# TMS34010_Adapter_for_DE10_Nano.net
KiCad netlist of a schematic drawn in EAGLE
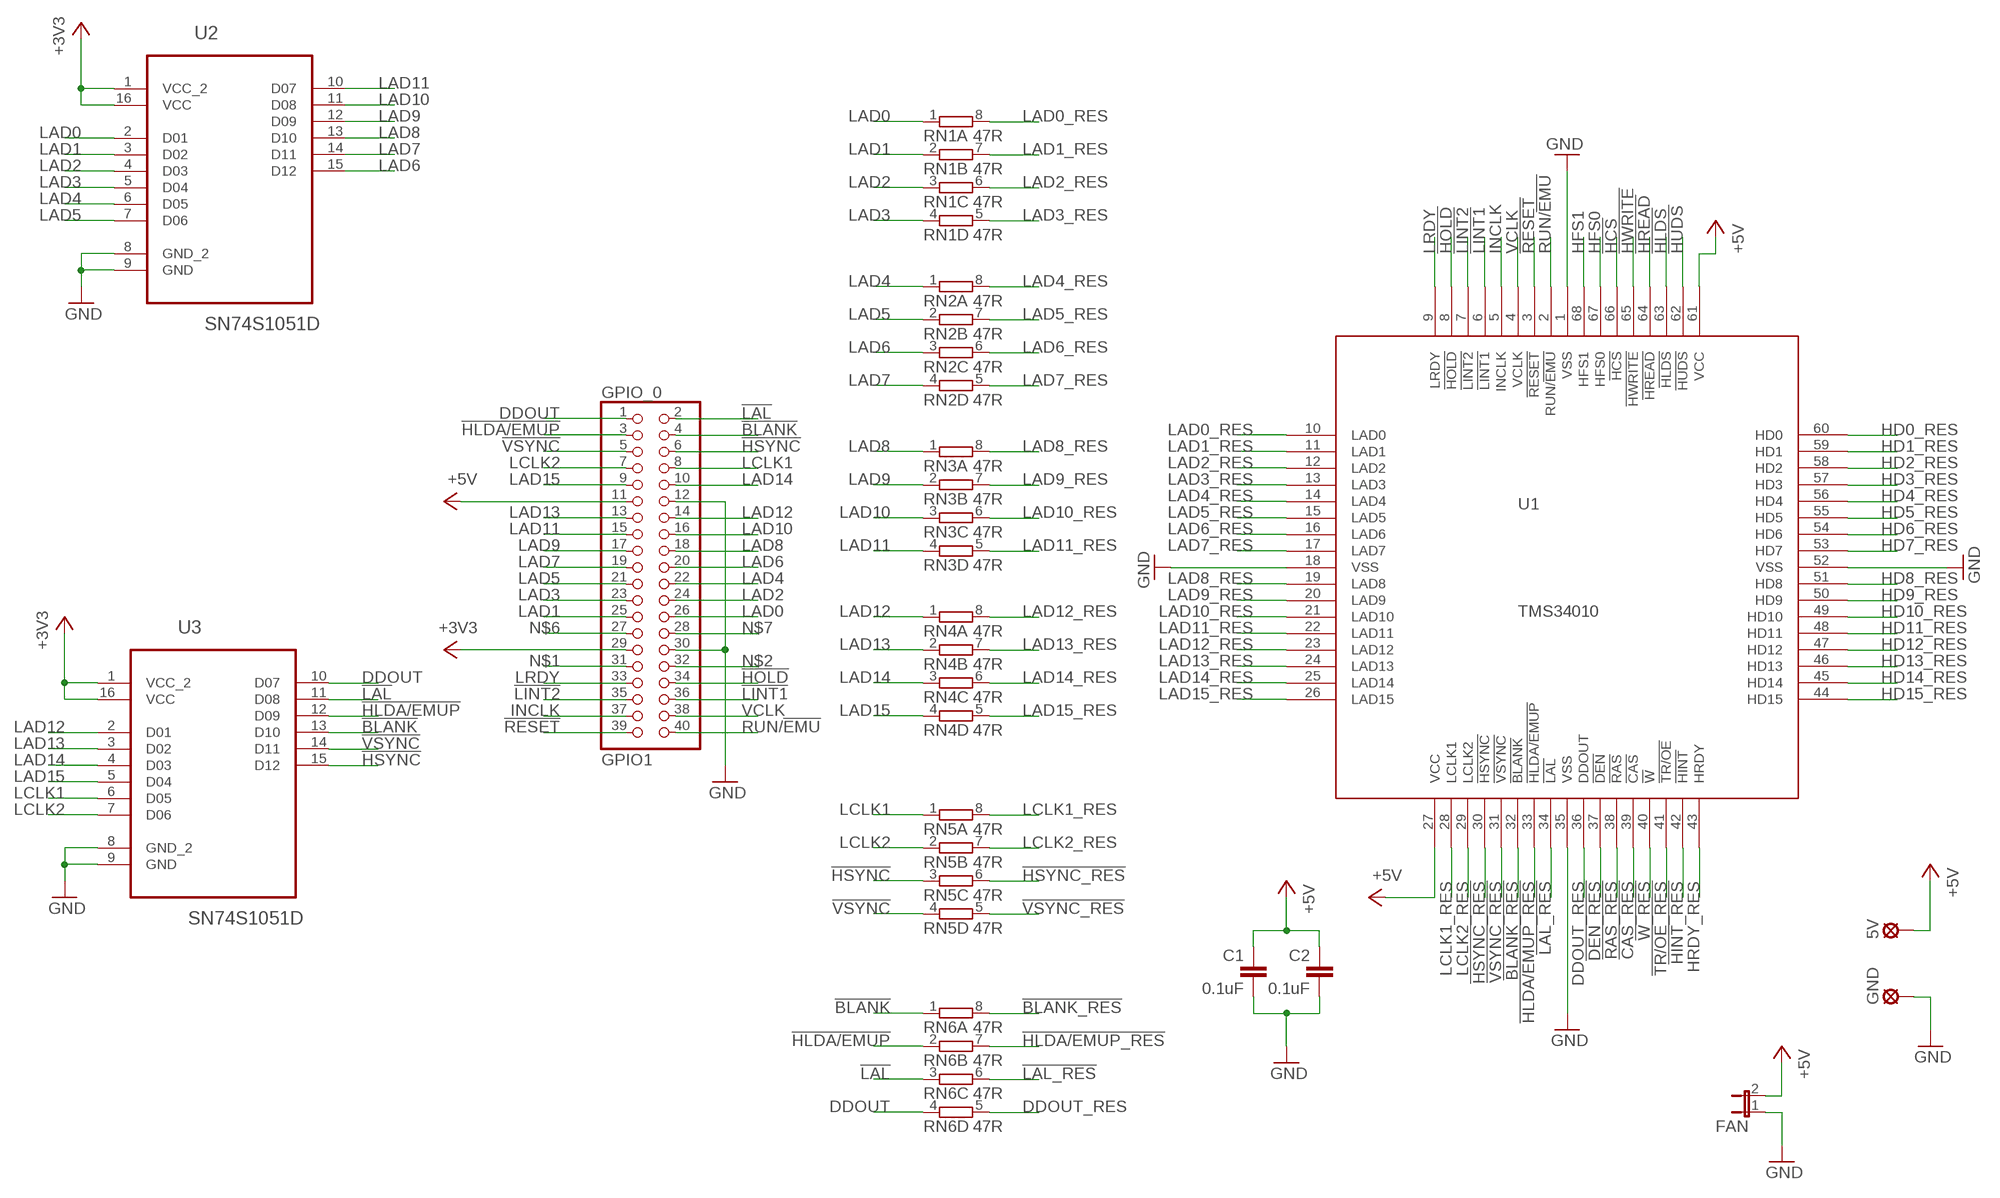
[diagram p0: schematic, sheet 1, part 1 of 2]
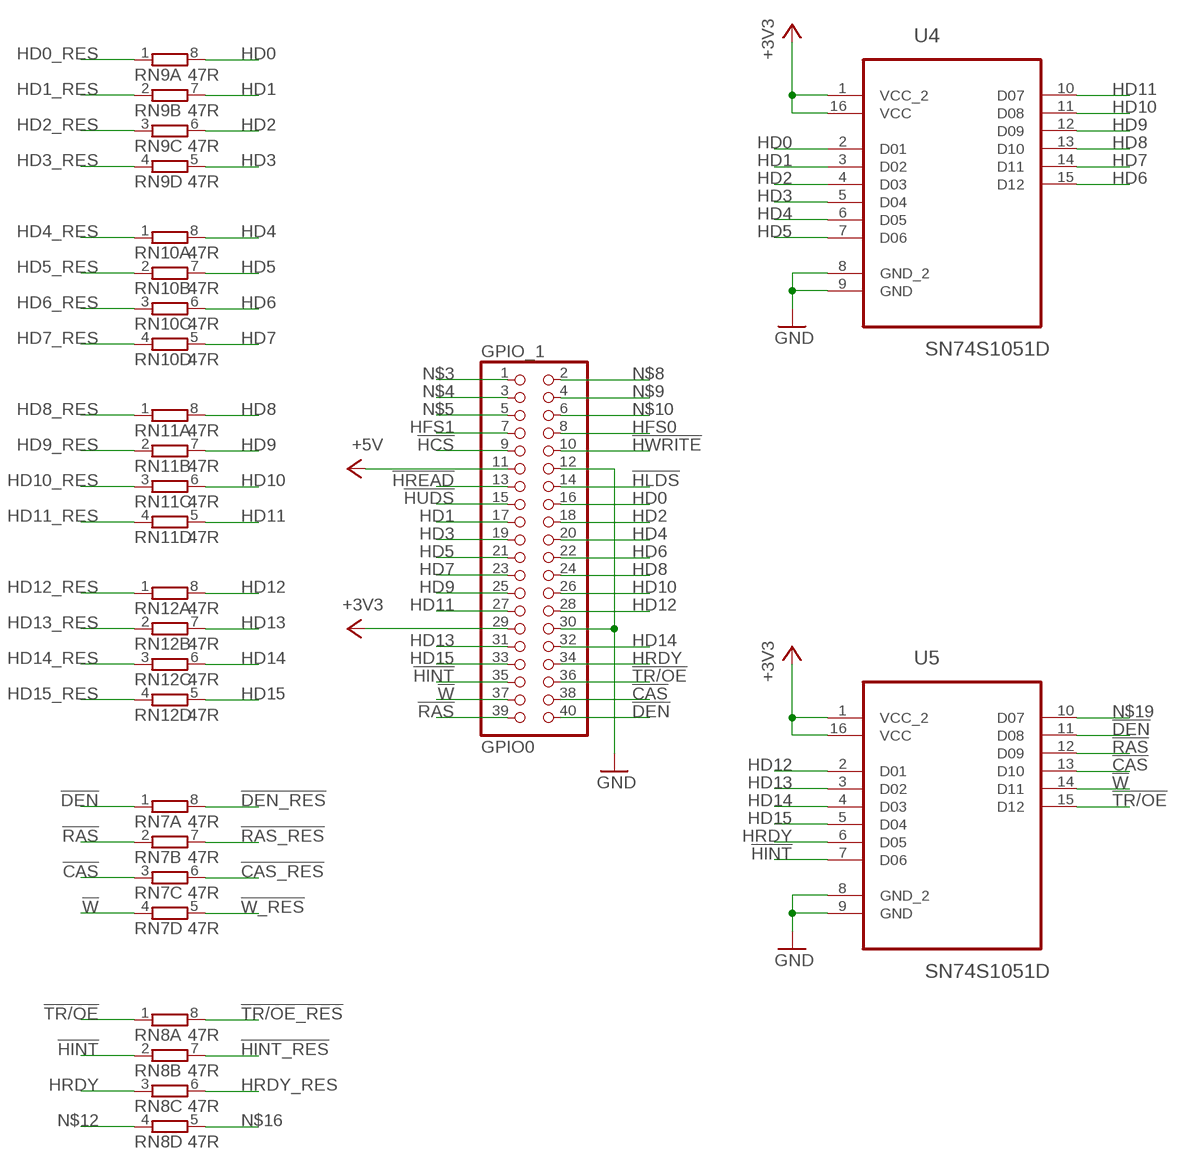
[diagram p1: schematic, sheet 1, part 2 of 2]

(export (version "E")
  (design (tool "Eeschema 10.0.6"))
  (components
    (comp (ref "5V")
      (value "LSP13")
      (footprint "eagle-import:LSP13")
      (libsource (lib "eagle-import") (part "LSP13"))
    )
    (comp (ref "C1")
      (value "0.1uF")
      (footprint "eagle-import:C0603")
      (libsource (lib "eagle-import") (part "C-EUC0603"))
    )
    (comp (ref "C2")
      (value "0.1uF")
      (footprint "eagle-import:C0603")
      (libsource (lib "eagle-import") (part "C-EUC0603"))
    )
    (comp (ref "FAN")
      (value "JP1E")
      (footprint "eagle-import:JP1")
      (libsource (lib "eagle-import") (part "JP1E"))
    )
    (comp (ref "GND")
      (value "LSP13")
      (footprint "eagle-import:LSP13")
      (libsource (lib "eagle-import") (part "LSP13"))
    )
    (comp (ref "GPIO_0")
      (value "GPIO1")
      (footprint "eagle-import:2X20")
      (libsource (lib "eagle-import") (part "PINHD-2X20"))
    )
    (comp (ref "GPIO_1")
      (value "GPIO0")
      (footprint "eagle-import:2X20")
      (libsource (lib "eagle-import") (part "PINHD-2X20"))
    )
    (comp (ref "RN1")
      (value "47R")
      (footprint "eagle-import:EXBV8V")
      (libsource (lib "eagle-import") (part "4R-NEXBV8V"))
    )
    (comp (ref "RN2")
      (value "47R")
      (footprint "eagle-import:EXBV8V")
      (libsource (lib "eagle-import") (part "4R-NEXBV8V"))
    )
    (comp (ref "RN3")
      (value "47R")
      (footprint "eagle-import:EXBV8V")
      (libsource (lib "eagle-import") (part "4R-NEXBV8V"))
    )
    (comp (ref "RN4")
      (value "47R")
      (footprint "eagle-import:EXBV8V")
      (libsource (lib "eagle-import") (part "4R-NEXBV8V"))
    )
    (comp (ref "RN5")
      (value "47R")
      (footprint "eagle-import:EXBV8V")
      (libsource (lib "eagle-import") (part "4R-NEXBV8V"))
    )
    (comp (ref "RN6")
      (value "47R")
      (footprint "eagle-import:EXBV8V")
      (libsource (lib "eagle-import") (part "4R-NEXBV8V"))
    )
    (comp (ref "RN7")
      (value "47R")
      (footprint "eagle-import:EXBV8V")
      (libsource (lib "eagle-import") (part "4R-NEXBV8V"))
    )
    (comp (ref "RN8")
      (value "47R")
      (footprint "eagle-import:EXBV8V")
      (libsource (lib "eagle-import") (part "4R-NEXBV8V"))
    )
    (comp (ref "RN9")
      (value "47R")
      (footprint "eagle-import:EXBV8V")
      (libsource (lib "eagle-import") (part "4R-NEXBV8V"))
    )
    (comp (ref "RN10")
      (value "47R")
      (footprint "eagle-import:EXBV8V")
      (libsource (lib "eagle-import") (part "4R-NEXBV8V"))
    )
    (comp (ref "RN11")
      (value "47R")
      (footprint "eagle-import:EXBV8V")
      (libsource (lib "eagle-import") (part "4R-NEXBV8V"))
    )
    (comp (ref "RN12")
      (value "47R")
      (footprint "eagle-import:EXBV8V")
      (libsource (lib "eagle-import") (part "4R-NEXBV8V"))
    )
    (comp (ref "U1")
      (value "TMS34010")
      (footprint "eagle-import:PLCC68")
      (libsource (lib "eagle-import") (part "TMS34010"))
    )
    (comp (ref "U2")
      (value "SN74S1051D")
      (footprint "eagle-import:SOIC127P600X175-16N")
      (libsource (lib "eagle-import") (part "SN74S1051D"))
    )
    (comp (ref "U3")
      (value "SN74S1051D")
      (footprint "eagle-import:SOIC127P600X175-16N")
      (libsource (lib "eagle-import") (part "SN74S1051D"))
    )
    (comp (ref "U4")
      (value "SN74S1051D")
      (footprint "eagle-import:SOIC127P600X175-16N")
      (libsource (lib "eagle-import") (part "SN74S1051D"))
    )
    (comp (ref "U5")
      (value "SN74S1051D")
      (footprint "eagle-import:SOIC127P600X175-16N")
      (libsource (lib "eagle-import") (part "SN74S1051D"))
    )
  )
  (nets
    (net (code "1") (name "+3V3") (class "Default")
      (node (ref "GPIO_0") (pin "29") (pinfunction "29_29") (pintype "passive"))
      (node (ref "GPIO_1") (pin "29") (pinfunction "29_29") (pintype "passive"))
      (node (ref "U2") (pin "1") (pinfunction "VCC_2_1") (pintype "power_in"))
      (node (ref "U2") (pin "16") (pinfunction "VCC_16") (pintype "power_in"))
      (node (ref "U3") (pin "1") (pinfunction "VCC_2_1") (pintype "power_in"))
      (node (ref "U3") (pin "16") (pinfunction "VCC_16") (pintype "power_in"))
      (node (ref "U4") (pin "1") (pinfunction "VCC_2_1") (pintype "power_in"))
      (node (ref "U4") (pin "16") (pinfunction "VCC_16") (pintype "power_in"))
      (node (ref "U5") (pin "1") (pinfunction "VCC_2_1") (pintype "power_in"))
      (node (ref "U5") (pin "16") (pinfunction "VCC_16") (pintype "power_in"))
    )
    (net (code "2") (name "+5V") (class "Default")
      (node (ref "5V") (pin "MP") (pinfunction "MP_MP") (pintype "passive"))
      (node (ref "C1") (pin "1") (pinfunction "1_1") (pintype "passive"))
      (node (ref "C2") (pin "1") (pinfunction "1_1") (pintype "passive"))
      (node (ref "FAN") (pin "2") (pinfunction "2_2") (pintype "passive"))
      (node (ref "GPIO_0") (pin "11") (pinfunction "11_11") (pintype "passive"))
      (node (ref "GPIO_1") (pin "11") (pinfunction "11_11") (pintype "passive"))
      (node (ref "U1") (pin "27") (pinfunction "VCC_27") (pintype "power_in"))
      (node (ref "U1") (pin "61") (pinfunction "VCC_61") (pintype "power_in"))
    )
    (net (code "3") (name "/DDOUT") (class "Default")
      (node (ref "GPIO_0") (pin "1") (pinfunction "1_1") (pintype "passive"))
      (node (ref "RN6") (pin "4") (pinfunction "1_4") (pintype "passive"))
      (node (ref "U3") (pin "10") (pinfunction "D07_10") (pintype "bidirectional"))
    )
    (net (code "4") (name "/DDOUT_RES") (class "Default")
      (node (ref "RN6") (pin "5") (pinfunction "2_5") (pintype "passive"))
      (node (ref "U1") (pin "36") (pinfunction "DDOUT_36") (pintype "output"))
    )
    (net (code "5") (name "/HD0") (class "Default")
      (node (ref "GPIO_1") (pin "16") (pinfunction "16_16") (pintype "passive"))
      (node (ref "RN9") (pin "8") (pinfunction "2_8") (pintype "passive"))
      (node (ref "U4") (pin "2") (pinfunction "D01_2") (pintype "bidirectional"))
    )
    (net (code "6") (name "/HD0_RES") (class "Default")
      (node (ref "RN9") (pin "1") (pinfunction "1_1") (pintype "passive"))
      (node (ref "U1") (pin "60") (pinfunction "HD0_60") (pintype "bidirectional"))
    )
    (net (code "7") (name "/HD1") (class "Default")
      (node (ref "GPIO_1") (pin "17") (pinfunction "17_17") (pintype "passive"))
      (node (ref "RN9") (pin "7") (pinfunction "2_7") (pintype "passive"))
      (node (ref "U4") (pin "3") (pinfunction "D02_3") (pintype "bidirectional"))
    )
    (net (code "8") (name "/HD1_RES") (class "Default")
      (node (ref "RN9") (pin "2") (pinfunction "1_2") (pintype "passive"))
      (node (ref "U1") (pin "59") (pinfunction "HD1_59") (pintype "bidirectional"))
    )
    (net (code "9") (name "/HD2") (class "Default")
      (node (ref "GPIO_1") (pin "18") (pinfunction "18_18") (pintype "passive"))
      (node (ref "RN9") (pin "6") (pinfunction "2_6") (pintype "passive"))
      (node (ref "U4") (pin "4") (pinfunction "D03_4") (pintype "bidirectional"))
    )
    (net (code "10") (name "/HD2_RES") (class "Default")
      (node (ref "RN9") (pin "3") (pinfunction "1_3") (pintype "passive"))
      (node (ref "U1") (pin "58") (pinfunction "HD2_58") (pintype "bidirectional"))
    )
    (net (code "11") (name "/HD3") (class "Default")
      (node (ref "GPIO_1") (pin "19") (pinfunction "19_19") (pintype "passive"))
      (node (ref "RN9") (pin "5") (pinfunction "2_5") (pintype "passive"))
      (node (ref "U4") (pin "5") (pinfunction "D04_5") (pintype "bidirectional"))
    )
    (net (code "12") (name "/HD3_RES") (class "Default")
      (node (ref "RN9") (pin "4") (pinfunction "1_4") (pintype "passive"))
      (node (ref "U1") (pin "57") (pinfunction "HD3_57") (pintype "bidirectional"))
    )
    (net (code "13") (name "/HD4") (class "Default")
      (node (ref "GPIO_1") (pin "20") (pinfunction "20_20") (pintype "passive"))
      (node (ref "RN10") (pin "8") (pinfunction "2_8") (pintype "passive"))
      (node (ref "U4") (pin "6") (pinfunction "D05_6") (pintype "bidirectional"))
    )
    (net (code "14") (name "/HD4_RES") (class "Default")
      (node (ref "RN10") (pin "1") (pinfunction "1_1") (pintype "passive"))
      (node (ref "U1") (pin "56") (pinfunction "HD4_56") (pintype "bidirectional"))
    )
    (net (code "15") (name "/HD5") (class "Default")
      (node (ref "GPIO_1") (pin "21") (pinfunction "21_21") (pintype "passive"))
      (node (ref "RN10") (pin "7") (pinfunction "2_7") (pintype "passive"))
      (node (ref "U4") (pin "7") (pinfunction "D06_7") (pintype "bidirectional"))
    )
    (net (code "16") (name "/HD5_RES") (class "Default")
      (node (ref "RN10") (pin "2") (pinfunction "1_2") (pintype "passive"))
      (node (ref "U1") (pin "55") (pinfunction "HD5_55") (pintype "bidirectional"))
    )
    (net (code "17") (name "/HD6") (class "Default")
      (node (ref "GPIO_1") (pin "22") (pinfunction "22_22") (pintype "passive"))
      (node (ref "RN10") (pin "6") (pinfunction "2_6") (pintype "passive"))
      (node (ref "U4") (pin "15") (pinfunction "D12_15") (pintype "bidirectional"))
    )
    (net (code "18") (name "/HD6_RES") (class "Default")
      (node (ref "RN10") (pin "3") (pinfunction "1_3") (pintype "passive"))
      (node (ref "U1") (pin "54") (pinfunction "HD6_54") (pintype "bidirectional"))
    )
    (net (code "19") (name "/HD7") (class "Default")
      (node (ref "GPIO_1") (pin "23") (pinfunction "23_23") (pintype "passive"))
      (node (ref "RN10") (pin "5") (pinfunction "2_5") (pintype "passive"))
      (node (ref "U4") (pin "14") (pinfunction "D11_14") (pintype "bidirectional"))
    )
    (net (code "20") (name "/HD7_RES") (class "Default")
      (node (ref "RN10") (pin "4") (pinfunction "1_4") (pintype "passive"))
      (node (ref "U1") (pin "53") (pinfunction "HD7_53") (pintype "bidirectional"))
    )
    (net (code "21") (name "/HD8") (class "Default")
      (node (ref "GPIO_1") (pin "24") (pinfunction "24_24") (pintype "passive"))
      (node (ref "RN11") (pin "8") (pinfunction "2_8") (pintype "passive"))
      (node (ref "U4") (pin "13") (pinfunction "D10_13") (pintype "bidirectional"))
    )
    (net (code "22") (name "/HD8_RES") (class "Default")
      (node (ref "RN11") (pin "1") (pinfunction "1_1") (pintype "passive"))
      (node (ref "U1") (pin "51") (pinfunction "HD8_51") (pintype "bidirectional"))
    )
    (net (code "23") (name "/HD9") (class "Default")
      (node (ref "GPIO_1") (pin "25") (pinfunction "25_25") (pintype "passive"))
      (node (ref "RN11") (pin "7") (pinfunction "2_7") (pintype "passive"))
      (node (ref "U4") (pin "12") (pinfunction "D09_12") (pintype "bidirectional"))
    )
    (net (code "24") (name "/HD9_RES") (class "Default")
      (node (ref "RN11") (pin "2") (pinfunction "1_2") (pintype "passive"))
      (node (ref "U1") (pin "50") (pinfunction "HD9_50") (pintype "bidirectional"))
    )
    (net (code "25") (name "/HD10") (class "Default")
      (node (ref "GPIO_1") (pin "26") (pinfunction "26_26") (pintype "passive"))
      (node (ref "RN11") (pin "6") (pinfunction "2_6") (pintype "passive"))
      (node (ref "U4") (pin "11") (pinfunction "D08_11") (pintype "bidirectional"))
    )
    (net (code "26") (name "/HD10_RES") (class "Default")
      (node (ref "RN11") (pin "3") (pinfunction "1_3") (pintype "passive"))
      (node (ref "U1") (pin "49") (pinfunction "HD10_49") (pintype "bidirectional"))
    )
    (net (code "27") (name "/HD11") (class "Default")
      (node (ref "GPIO_1") (pin "27") (pinfunction "27_27") (pintype "passive"))
      (node (ref "RN11") (pin "5") (pinfunction "2_5") (pintype "passive"))
      (node (ref "U4") (pin "10") (pinfunction "D07_10") (pintype "bidirectional"))
    )
    (net (code "28") (name "/HD11_RES") (class "Default")
      (node (ref "RN11") (pin "4") (pinfunction "1_4") (pintype "passive"))
      (node (ref "U1") (pin "48") (pinfunction "HD11_48") (pintype "bidirectional"))
    )
    (net (code "29") (name "/HD12") (class "Default")
      (node (ref "GPIO_1") (pin "28") (pinfunction "28_28") (pintype "passive"))
      (node (ref "RN12") (pin "8") (pinfunction "2_8") (pintype "passive"))
      (node (ref "U5") (pin "2") (pinfunction "D01_2") (pintype "bidirectional"))
    )
    (net (code "30") (name "/HD12_RES") (class "Default")
      (node (ref "RN12") (pin "1") (pinfunction "1_1") (pintype "passive"))
      (node (ref "U1") (pin "47") (pinfunction "HD12_47") (pintype "bidirectional"))
    )
    (net (code "31") (name "/HD13") (class "Default")
      (node (ref "GPIO_1") (pin "31") (pinfunction "31_31") (pintype "passive"))
      (node (ref "RN12") (pin "7") (pinfunction "2_7") (pintype "passive"))
      (node (ref "U5") (pin "3") (pinfunction "D02_3") (pintype "bidirectional"))
    )
    (net (code "32") (name "/HD13_RES") (class "Default")
      (node (ref "RN12") (pin "2") (pinfunction "1_2") (pintype "passive"))
      (node (ref "U1") (pin "46") (pinfunction "HD13_46") (pintype "bidirectional"))
    )
    (net (code "33") (name "/HD14") (class "Default")
      (node (ref "GPIO_1") (pin "32") (pinfunction "32_32") (pintype "passive"))
      (node (ref "RN12") (pin "6") (pinfunction "2_6") (pintype "passive"))
      (node (ref "U5") (pin "4") (pinfunction "D03_4") (pintype "bidirectional"))
    )
    (net (code "34") (name "/HD14_RES") (class "Default")
      (node (ref "RN12") (pin "3") (pinfunction "1_3") (pintype "passive"))
      (node (ref "U1") (pin "45") (pinfunction "HD14_45") (pintype "bidirectional"))
    )
    (net (code "35") (name "/HD15") (class "Default")
      (node (ref "GPIO_1") (pin "33") (pinfunction "33_33") (pintype "passive"))
      (node (ref "RN12") (pin "5") (pinfunction "2_5") (pintype "passive"))
      (node (ref "U5") (pin "5") (pinfunction "D04_5") (pintype "bidirectional"))
    )
    (net (code "36") (name "/HD15_RES") (class "Default")
      (node (ref "RN12") (pin "4") (pinfunction "1_4") (pintype "passive"))
      (node (ref "U1") (pin "44") (pinfunction "HD15_44") (pintype "bidirectional"))
    )
    (net (code "37") (name "/HFS0") (class "Default")
      (node (ref "GPIO_1") (pin "8") (pinfunction "8_8") (pintype "passive"))
      (node (ref "U1") (pin "67") (pinfunction "HFS0_67") (pintype "input"))
    )
    (net (code "38") (name "/HFS1") (class "Default")
      (node (ref "GPIO_1") (pin "7") (pinfunction "7_7") (pintype "passive"))
      (node (ref "U1") (pin "68") (pinfunction "HFS1_68") (pintype "input"))
    )
    (net (code "39") (name "/HRDY") (class "Default")
      (node (ref "GPIO_1") (pin "34") (pinfunction "34_34") (pintype "passive"))
      (node (ref "RN8") (pin "3") (pinfunction "1_3") (pintype "passive"))
      (node (ref "U5") (pin "6") (pinfunction "D05_6") (pintype "bidirectional"))
    )
    (net (code "40") (name "/HRDY_RES") (class "Default")
      (node (ref "RN8") (pin "6") (pinfunction "2_6") (pintype "passive"))
      (node (ref "U1") (pin "43") (pinfunction "HRDY_43") (pintype "output"))
    )
    (net (code "41") (name "/INCLK") (class "Default")
      (node (ref "GPIO_0") (pin "37") (pinfunction "37_37") (pintype "passive"))
      (node (ref "U1") (pin "5") (pinfunction "INCLK_5") (pintype "input"))
    )
    (net (code "42") (name "/LAD0") (class "Default")
      (node (ref "GPIO_0") (pin "26") (pinfunction "26_26") (pintype "passive"))
      (node (ref "RN1") (pin "1") (pinfunction "1_1") (pintype "passive"))
      (node (ref "U2") (pin "2") (pinfunction "D01_2") (pintype "bidirectional"))
    )
    (net (code "43") (name "/LAD0_RES") (class "Default")
      (node (ref "RN1") (pin "8") (pinfunction "2_8") (pintype "passive"))
      (node (ref "U1") (pin "10") (pinfunction "LAD0_10") (pintype "bidirectional"))
    )
    (net (code "44") (name "/LAD1") (class "Default")
      (node (ref "GPIO_0") (pin "25") (pinfunction "25_25") (pintype "passive"))
      (node (ref "RN1") (pin "2") (pinfunction "1_2") (pintype "passive"))
      (node (ref "U2") (pin "3") (pinfunction "D02_3") (pintype "bidirectional"))
    )
    (net (code "45") (name "/LAD1_RES") (class "Default")
      (node (ref "RN1") (pin "7") (pinfunction "2_7") (pintype "passive"))
      (node (ref "U1") (pin "11") (pinfunction "LAD1_11") (pintype "bidirectional"))
    )
    (net (code "46") (name "/LAD2") (class "Default")
      (node (ref "GPIO_0") (pin "24") (pinfunction "24_24") (pintype "passive"))
      (node (ref "RN1") (pin "3") (pinfunction "1_3") (pintype "passive"))
      (node (ref "U2") (pin "4") (pinfunction "D03_4") (pintype "bidirectional"))
    )
    (net (code "47") (name "/LAD2_RES") (class "Default")
      (node (ref "RN1") (pin "6") (pinfunction "2_6") (pintype "passive"))
      (node (ref "U1") (pin "12") (pinfunction "LAD2_12") (pintype "bidirectional"))
    )
    (net (code "48") (name "/LAD3") (class "Default")
      (node (ref "GPIO_0") (pin "23") (pinfunction "23_23") (pintype "passive"))
      (node (ref "RN1") (pin "4") (pinfunction "1_4") (pintype "passive"))
      (node (ref "U2") (pin "5") (pinfunction "D04_5") (pintype "bidirectional"))
    )
    (net (code "49") (name "/LAD3_RES") (class "Default")
      (node (ref "RN1") (pin "5") (pinfunction "2_5") (pintype "passive"))
      (node (ref "U1") (pin "13") (pinfunction "LAD3_13") (pintype "bidirectional"))
    )
    (net (code "50") (name "/LAD4") (class "Default")
      (node (ref "GPIO_0") (pin "22") (pinfunction "22_22") (pintype "passive"))
      (node (ref "RN2") (pin "1") (pinfunction "1_1") (pintype "passive"))
      (node (ref "U2") (pin "6") (pinfunction "D05_6") (pintype "bidirectional"))
    )
    (net (code "51") (name "/LAD4_RES") (class "Default")
      (node (ref "RN2") (pin "8") (pinfunction "2_8") (pintype "passive"))
      (node (ref "U1") (pin "14") (pinfunction "LAD4_14") (pintype "bidirectional"))
    )
    (net (code "52") (name "/LAD5") (class "Default")
      (node (ref "GPIO_0") (pin "21") (pinfunction "21_21") (pintype "passive"))
      (node (ref "RN2") (pin "2") (pinfunction "1_2") (pintype "passive"))
      (node (ref "U2") (pin "7") (pinfunction "D06_7") (pintype "bidirectional"))
    )
    (net (code "53") (name "/LAD5_RES") (class "Default")
      (node (ref "RN2") (pin "7") (pinfunction "2_7") (pintype "passive"))
      (node (ref "U1") (pin "15") (pinfunction "LAD5_15") (pintype "bidirectional"))
    )
    (net (code "54") (name "/LAD6") (class "Default")
      (node (ref "GPIO_0") (pin "20") (pinfunction "20_20") (pintype "passive"))
      (node (ref "RN2") (pin "3") (pinfunction "1_3") (pintype "passive"))
      (node (ref "U2") (pin "15") (pinfunction "D12_15") (pintype "bidirectional"))
    )
    (net (code "55") (name "/LAD6_RES") (class "Default")
      (node (ref "RN2") (pin "6") (pinfunction "2_6") (pintype "passive"))
      (node (ref "U1") (pin "16") (pinfunction "LAD6_16") (pintype "bidirectional"))
    )
    (net (code "56") (name "/LAD7") (class "Default")
      (node (ref "GPIO_0") (pin "19") (pinfunction "19_19") (pintype "passive"))
      (node (ref "RN2") (pin "4") (pinfunction "1_4") (pintype "passive"))
      (node (ref "U2") (pin "14") (pinfunction "D11_14") (pintype "bidirectional"))
    )
    (net (code "57") (name "/LAD7_RES") (class "Default")
      (node (ref "RN2") (pin "5") (pinfunction "2_5") (pintype "passive"))
      (node (ref "U1") (pin "17") (pinfunction "LAD7_17") (pintype "bidirectional"))
    )
    (net (code "58") (name "/LAD8") (class "Default")
      (node (ref "GPIO_0") (pin "18") (pinfunction "18_18") (pintype "passive"))
      (node (ref "RN3") (pin "1") (pinfunction "1_1") (pintype "passive"))
      (node (ref "U2") (pin "13") (pinfunction "D10_13") (pintype "bidirectional"))
    )
    (net (code "59") (name "/LAD8_RES") (class "Default")
      (node (ref "RN3") (pin "8") (pinfunction "2_8") (pintype "passive"))
      (node (ref "U1") (pin "19") (pinfunction "LAD8_19") (pintype "bidirectional"))
    )
    (net (code "60") (name "/LAD9") (class "Default")
      (node (ref "GPIO_0") (pin "17") (pinfunction "17_17") (pintype "passive"))
      (node (ref "RN3") (pin "2") (pinfunction "1_2") (pintype "passive"))
      (node (ref "U2") (pin "12") (pinfunction "D09_12") (pintype "bidirectional"))
    )
    (net (code "61") (name "/LAD9_RES") (class "Default")
      (node (ref "RN3") (pin "7") (pinfunction "2_7") (pintype "passive"))
      (node (ref "U1") (pin "20") (pinfunction "LAD9_20") (pintype "bidirectional"))
    )
    (net (code "62") (name "/LAD10") (class "Default")
      (node (ref "GPIO_0") (pin "16") (pinfunction "16_16") (pintype "passive"))
      (node (ref "RN3") (pin "3") (pinfunction "1_3") (pintype "passive"))
      (node (ref "U2") (pin "11") (pinfunction "D08_11") (pintype "bidirectional"))
    )
    (net (code "63") (name "/LAD10_RES") (class "Default")
      (node (ref "RN3") (pin "6") (pinfunction "2_6") (pintype "passive"))
      (node (ref "U1") (pin "21") (pinfunction "LAD10_21") (pintype "bidirectional"))
    )
    (net (code "64") (name "/LAD11") (class "Default")
      (node (ref "GPIO_0") (pin "15") (pinfunction "15_15") (pintype "passive"))
      (node (ref "RN3") (pin "4") (pinfunction "1_4") (pintype "passive"))
      (node (ref "U2") (pin "10") (pinfunction "D07_10") (pintype "bidirectional"))
    )
    (net (code "65") (name "/LAD11_RES") (class "Default")
      (node (ref "RN3") (pin "5") (pinfunction "2_5") (pintype "passive"))
      (node (ref "U1") (pin "22") (pinfunction "LAD11_22") (pintype "bidirectional"))
    )
    (net (code "66") (name "/LAD12") (class "Default")
      (node (ref "GPIO_0") (pin "14") (pinfunction "14_14") (pintype "passive"))
      (node (ref "RN4") (pin "1") (pinfunction "1_1") (pintype "passive"))
      (node (ref "U3") (pin "2") (pinfunction "D01_2") (pintype "bidirectional"))
    )
    (net (code "67") (name "/LAD12_RES") (class "Default")
      (node (ref "RN4") (pin "8") (pinfunction "2_8") (pintype "passive"))
      (node (ref "U1") (pin "23") (pinfunction "LAD12_23") (pintype "bidirectional"))
    )
    (net (code "68") (name "/LAD13") (class "Default")
      (node (ref "GPIO_0") (pin "13") (pinfunction "13_13") (pintype "passive"))
      (node (ref "RN4") (pin "2") (pinfunction "1_2") (pintype "passive"))
      (node (ref "U3") (pin "3") (pinfunction "D02_3") (pintype "bidirectional"))
    )
    (net (code "69") (name "/LAD13_RES") (class "Default")
      (node (ref "RN4") (pin "7") (pinfunction "2_7") (pintype "passive"))
      (node (ref "U1") (pin "24") (pinfunction "LAD13_24") (pintype "bidirectional"))
    )
    (net (code "70") (name "/LAD14") (class "Default")
      (node (ref "GPIO_0") (pin "10") (pinfunction "10_10") (pintype "passive"))
      (node (ref "RN4") (pin "3") (pinfunction "1_3") (pintype "passive"))
      (node (ref "U3") (pin "4") (pinfunction "D03_4") (pintype "bidirectional"))
    )
    (net (code "71") (name "/LAD14_RES") (class "Default")
      (node (ref "RN4") (pin "6") (pinfunction "2_6") (pintype "passive"))
      (node (ref "U1") (pin "25") (pinfunction "LAD14_25") (pintype "bidirectional"))
    )
    (net (code "72") (name "/LAD15") (class "Default")
      (node (ref "GPIO_0") (pin "9") (pinfunction "9_9") (pintype "passive"))
      (node (ref "RN4") (pin "4") (pinfunction "1_4") (pintype "passive"))
      (node (ref "U3") (pin "5") (pinfunction "D04_5") (pintype "bidirectional"))
    )
    (net (code "73") (name "/LAD15_RES") (class "Default")
      (node (ref "RN4") (pin "5") (pinfunction "2_5") (pintype "passive"))
      (node (ref "U1") (pin "26") (pinfunction "LAD15_26") (pintype "bidirectional"))
    )
    (net (code "74") (name "/LCLK1") (class "Default")
      (node (ref "GPIO_0") (pin "8") (pinfunction "8_8") (pintype "passive"))
      (node (ref "RN5") (pin "1") (pinfunction "1_1") (pintype "passive"))
      (node (ref "U3") (pin "6") (pinfunction "D05_6") (pintype "bidirectional"))
    )
    (net (code "75") (name "/LCLK1_RES") (class "Default")
      (node (ref "RN5") (pin "8") (pinfunction "2_8") (pintype "passive"))
      (node (ref "U1") (pin "28") (pinfunction "LCLK1_28") (pintype "output"))
    )
    (net (code "76") (name "/LCLK2") (class "Default")
      (node (ref "GPIO_0") (pin "7") (pinfunction "7_7") (pintype "passive"))
      (node (ref "RN5") (pin "2") (pinfunction "1_2") (pintype "passive"))
      (node (ref "U3") (pin "7") (pinfunction "D06_7") (pintype "bidirectional"))
    )
    (net (code "77") (name "/LCLK2_RES") (class "Default")
      (node (ref "RN5") (pin "7") (pinfunction "2_7") (pintype "passive"))
      (node (ref "U1") (pin "29") (pinfunction "LCLK2_29") (pintype "output"))
    )
    (net (code "78") (name "/LRDY") (class "Default")
      (node (ref "GPIO_0") (pin "33") (pinfunction "33_33") (pintype "passive"))
      (node (ref "U1") (pin "9") (pinfunction "LRDY_9") (pintype "input"))
    )
    (net (code "79") (name "/N$1") (class "Default")
      (node (ref "GPIO_0") (pin "31") (pinfunction "31_31") (pintype "passive"))
    )
    (net (code "80") (name "/N$2") (class "Default")
      (node (ref "GPIO_0") (pin "32") (pinfunction "32_32") (pintype "passive"))
    )
    (net (code "81") (name "/N$3") (class "Default")
      (node (ref "GPIO_1") (pin "1") (pinfunction "1_1") (pintype "passive"))
    )
    (net (code "82") (name "/N$4") (class "Default")
      (node (ref "GPIO_1") (pin "3") (pinfunction "3_3") (pintype "passive"))
    )
    (net (code "83") (name "/N$5") (class "Default")
      (node (ref "GPIO_1") (pin "5") (pinfunction "5_5") (pintype "passive"))
    )
    (net (code "84") (name "/N$6") (class "Default")
      (node (ref "GPIO_0") (pin "27") (pinfunction "27_27") (pintype "passive"))
    )
    (net (code "85") (name "/N$7") (class "Default")
      (node (ref "GPIO_0") (pin "28") (pinfunction "28_28") (pintype "passive"))
    )
    (net (code "86") (name "/N$8") (class "Default")
      (node (ref "GPIO_1") (pin "2") (pinfunction "2_2") (pintype "passive"))
    )
    (net (code "87") (name "/N$9") (class "Default")
      (node (ref "GPIO_1") (pin "4") (pinfunction "4_4") (pintype "passive"))
    )
    (net (code "88") (name "/N$10") (class "Default")
      (node (ref "GPIO_1") (pin "6") (pinfunction "6_6") (pintype "passive"))
    )
    (net (code "89") (name "/N$12") (class "Default")
      (node (ref "RN8") (pin "4") (pinfunction "1_4") (pintype "passive"))
    )
    (net (code "90") (name "/N$16") (class "Default")
      (node (ref "RN8") (pin "5") (pinfunction "2_5") (pintype "passive"))
    )
    (net (code "91") (name "/N$19") (class "Default")
      (node (ref "U5") (pin "10") (pinfunction "D07_10") (pintype "bidirectional"))
    )
    (net (code "92") (name "/RUN{slash}~{EMU}") (class "Default")
      (node (ref "GPIO_0") (pin "40") (pinfunction "40_40") (pintype "passive"))
      (node (ref "U1") (pin "2") (pinfunction "RUN/~{EMU}_2") (pintype "input"))
    )
    (net (code "93") (name "/VCLK") (class "Default")
      (node (ref "GPIO_0") (pin "38") (pinfunction "38_38") (pintype "passive"))
      (node (ref "U1") (pin "4") (pinfunction "VCLK_4") (pintype "input"))
    )
    (net (code "94") (name "/~{BLANK_RES}") (class "Default")
      (node (ref "RN6") (pin "8") (pinfunction "2_8") (pintype "passive"))
      (node (ref "U1") (pin "32") (pinfunction "~{BLANK}_32") (pintype "output"))
    )
    (net (code "95") (name "/~{BLANK}") (class "Default")
      (node (ref "GPIO_0") (pin "4") (pinfunction "4_4") (pintype "passive"))
      (node (ref "RN6") (pin "1") (pinfunction "1_1") (pintype "passive"))
      (node (ref "U3") (pin "13") (pinfunction "D10_13") (pintype "bidirectional"))
    )
    (net (code "96") (name "/~{CAS_RES}") (class "Default")
      (node (ref "RN7") (pin "6") (pinfunction "2_6") (pintype "passive"))
      (node (ref "U1") (pin "39") (pinfunction "~{CAS}_39") (pintype "output"))
    )
    (net (code "97") (name "/~{CAS}") (class "Default")
      (node (ref "GPIO_1") (pin "38") (pinfunction "38_38") (pintype "passive"))
      (node (ref "RN7") (pin "3") (pinfunction "1_3") (pintype "passive"))
      (node (ref "U5") (pin "13") (pinfunction "D10_13") (pintype "bidirectional"))
    )
    (net (code "98") (name "/~{DEN_RES}") (class "Default")
      (node (ref "RN7") (pin "8") (pinfunction "2_8") (pintype "passive"))
      (node (ref "U1") (pin "37") (pinfunction "~{DEN}_37") (pintype "output"))
    )
    (net (code "99") (name "/~{DEN}") (class "Default")
      (node (ref "GPIO_1") (pin "40") (pinfunction "40_40") (pintype "passive"))
      (node (ref "RN7") (pin "1") (pinfunction "1_1") (pintype "passive"))
      (node (ref "U5") (pin "11") (pinfunction "D08_11") (pintype "bidirectional"))
    )
    (net (code "100") (name "/~{HCS}") (class "Default")
      (node (ref "GPIO_1") (pin "9") (pinfunction "9_9") (pintype "passive"))
      (node (ref "U1") (pin "66") (pinfunction "~{HCS}_66") (pintype "input"))
    )
    (net (code "101") (name "/~{HINT_RES}") (class "Default")
      (node (ref "RN8") (pin "7") (pinfunction "2_7") (pintype "passive"))
      (node (ref "U1") (pin "42") (pinfunction "~{HINT}_42") (pintype "output"))
    )
    (net (code "102") (name "/~{HINT}") (class "Default")
      (node (ref "GPIO_1") (pin "35") (pinfunction "35_35") (pintype "passive"))
      (node (ref "RN8") (pin "2") (pinfunction "1_2") (pintype "passive"))
      (node (ref "U5") (pin "7") (pinfunction "D06_7") (pintype "bidirectional"))
    )
    (net (code "103") (name "/~{HLDA{slash}EMUP_RES}") (class "Default")
      (node (ref "RN6") (pin "7") (pinfunction "2_7") (pintype "passive"))
      (node (ref "U1") (pin "33") (pinfunction "~{HLDA/EMUP}_33") (pintype "output"))
    )
    (net (code "104") (name "/~{HLDA{slash}EMUP}") (class "Default")
      (node (ref "GPIO_0") (pin "3") (pinfunction "3_3") (pintype "passive"))
      (node (ref "RN6") (pin "2") (pinfunction "1_2") (pintype "passive"))
      (node (ref "U3") (pin "12") (pinfunction "D09_12") (pintype "bidirectional"))
    )
    (net (code "105") (name "/~{HLDS}") (class "Default")
      (node (ref "GPIO_1") (pin "14") (pinfunction "14_14") (pintype "passive"))
      (node (ref "U1") (pin "63") (pinfunction "~{HLDS}_63") (pintype "input"))
    )
    (net (code "106") (name "/~{HOLD}") (class "Default")
      (node (ref "GPIO_0") (pin "34") (pinfunction "34_34") (pintype "passive"))
      (node (ref "U1") (pin "8") (pinfunction "~{HOLD}_8") (pintype "input"))
    )
    (net (code "107") (name "/~{HREAD}") (class "Default")
      (node (ref "GPIO_1") (pin "13") (pinfunction "13_13") (pintype "passive"))
      (node (ref "U1") (pin "64") (pinfunction "~{HREAD}_64") (pintype "input"))
    )
    (net (code "108") (name "/~{HSYNC_RES}") (class "Default")
      (node (ref "RN5") (pin "6") (pinfunction "2_6") (pintype "passive"))
      (node (ref "U1") (pin "30") (pinfunction "~{HSYNC}_30") (pintype "bidirectional"))
    )
    (net (code "109") (name "/~{HSYNC}") (class "Default")
      (node (ref "GPIO_0") (pin "6") (pinfunction "6_6") (pintype "passive"))
      (node (ref "RN5") (pin "3") (pinfunction "1_3") (pintype "passive"))
      (node (ref "U3") (pin "15") (pinfunction "D12_15") (pintype "bidirectional"))
    )
    (net (code "110") (name "/~{HUDS}") (class "Default")
      (node (ref "GPIO_1") (pin "15") (pinfunction "15_15") (pintype "passive"))
      (node (ref "U1") (pin "62") (pinfunction "~{HUDS}_62") (pintype "input"))
    )
    (net (code "111") (name "/~{HWRITE}") (class "Default")
      (node (ref "GPIO_1") (pin "10") (pinfunction "10_10") (pintype "passive"))
      (node (ref "U1") (pin "65") (pinfunction "~{HWRITE}_65") (pintype "input"))
    )
    (net (code "112") (name "/~{LAL_RES}") (class "Default")
      (node (ref "RN6") (pin "6") (pinfunction "2_6") (pintype "passive"))
      (node (ref "U1") (pin "34") (pinfunction "~{LAL}_34") (pintype "output"))
    )
    (net (code "113") (name "/~{LAL}") (class "Default")
      (node (ref "GPIO_0") (pin "2") (pinfunction "2_2") (pintype "passive"))
      (node (ref "RN6") (pin "3") (pinfunction "1_3") (pintype "passive"))
      (node (ref "U3") (pin "11") (pinfunction "D08_11") (pintype "bidirectional"))
    )
    (net (code "114") (name "/~{LINT1}") (class "Default")
      (node (ref "GPIO_0") (pin "36") (pinfunction "36_36") (pintype "passive"))
      (node (ref "U1") (pin "6") (pinfunction "~{LINT1}_6") (pintype "input"))
    )
    (net (code "115") (name "/~{LINT2}") (class "Default")
      (node (ref "GPIO_0") (pin "35") (pinfunction "35_35") (pintype "passive"))
      (node (ref "U1") (pin "7") (pinfunction "~{LINT2}_7") (pintype "input"))
    )
    (net (code "116") (name "/~{RAS_RES}") (class "Default")
      (node (ref "RN7") (pin "7") (pinfunction "2_7") (pintype "passive"))
      (node (ref "U1") (pin "38") (pinfunction "~{RAS}_38") (pintype "output"))
    )
    (net (code "117") (name "/~{RAS}") (class "Default")
      (node (ref "GPIO_1") (pin "39") (pinfunction "39_39") (pintype "passive"))
      (node (ref "RN7") (pin "2") (pinfunction "1_2") (pintype "passive"))
      (node (ref "U5") (pin "12") (pinfunction "D09_12") (pintype "bidirectional"))
    )
    (net (code "118") (name "/~{RESET}") (class "Default")
      (node (ref "GPIO_0") (pin "39") (pinfunction "39_39") (pintype "passive"))
      (node (ref "U1") (pin "3") (pinfunction "~{RESET}_3") (pintype "input"))
    )
    (net (code "119") (name "/~{TR{slash}OE_RES}") (class "Default")
      (node (ref "RN8") (pin "8") (pinfunction "2_8") (pintype "passive"))
      (node (ref "U1") (pin "41") (pinfunction "~{TR/OE}_41") (pintype "output"))
    )
    (net (code "120") (name "/~{TR{slash}OE}") (class "Default")
      (node (ref "GPIO_1") (pin "36") (pinfunction "36_36") (pintype "passive"))
      (node (ref "RN8") (pin "1") (pinfunction "1_1") (pintype "passive"))
      (node (ref "U5") (pin "15") (pinfunction "D12_15") (pintype "bidirectional"))
    )
    (net (code "121") (name "/~{VSYNC_RES}") (class "Default")
      (node (ref "RN5") (pin "5") (pinfunction "2_5") (pintype "passive"))
      (node (ref "U1") (pin "31") (pinfunction "~{VSYNC}_31") (pintype "bidirectional"))
    )
    (net (code "122") (name "/~{VSYNC}") (class "Default")
      (node (ref "GPIO_0") (pin "5") (pinfunction "5_5") (pintype "passive"))
      (node (ref "RN5") (pin "4") (pinfunction "1_4") (pintype "passive"))
      (node (ref "U3") (pin "14") (pinfunction "D11_14") (pintype "bidirectional"))
    )
    (net (code "123") (name "/~{W_RES}") (class "Default")
      (node (ref "RN7") (pin "5") (pinfunction "2_5") (pintype "passive"))
      (node (ref "U1") (pin "40") (pinfunction "~{W}_40") (pintype "output"))
    )
    (net (code "124") (name "/~{W}") (class "Default")
      (node (ref "GPIO_1") (pin "37") (pinfunction "37_37") (pintype "passive"))
      (node (ref "RN7") (pin "4") (pinfunction "1_4") (pintype "passive"))
      (node (ref "U5") (pin "14") (pinfunction "D11_14") (pintype "bidirectional"))
    )
    (net (code "125") (name "GND") (class "Default")
      (node (ref "C1") (pin "2") (pinfunction "2_2") (pintype "passive"))
      (node (ref "C2") (pin "2") (pinfunction "2_2") (pintype "passive"))
      (node (ref "FAN") (pin "1") (pinfunction "1_1") (pintype "passive"))
      (node (ref "GND") (pin "MP") (pinfunction "MP_MP") (pintype "passive"))
      (node (ref "GPIO_0") (pin "12") (pinfunction "12_12") (pintype "passive"))
      (node (ref "GPIO_0") (pin "30") (pinfunction "30_30") (pintype "passive"))
      (node (ref "GPIO_1") (pin "12") (pinfunction "12_12") (pintype "passive"))
      (node (ref "GPIO_1") (pin "30") (pinfunction "30_30") (pintype "passive"))
      (node (ref "U1") (pin "1") (pinfunction "VSS_1") (pintype "power_in"))
      (node (ref "U1") (pin "18") (pinfunction "VSS_18") (pintype "power_in"))
      (node (ref "U1") (pin "35") (pinfunction "VSS_35") (pintype "power_in"))
      (node (ref "U1") (pin "52") (pinfunction "VSS_52") (pintype "power_in"))
      (node (ref "U2") (pin "8") (pinfunction "GND_2_8") (pintype "passive"))
      (node (ref "U2") (pin "9") (pinfunction "GND_9") (pintype "passive"))
      (node (ref "U3") (pin "8") (pinfunction "GND_2_8") (pintype "passive"))
      (node (ref "U3") (pin "9") (pinfunction "GND_9") (pintype "passive"))
      (node (ref "U4") (pin "8") (pinfunction "GND_2_8") (pintype "passive"))
      (node (ref "U4") (pin "9") (pinfunction "GND_9") (pintype "passive"))
      (node (ref "U5") (pin "8") (pinfunction "GND_2_8") (pintype "passive"))
      (node (ref "U5") (pin "9") (pinfunction "GND_9") (pintype "passive"))
    )
  )
)
